# micro.net
KiCad netlist of a schematic drawn in Altium Designer
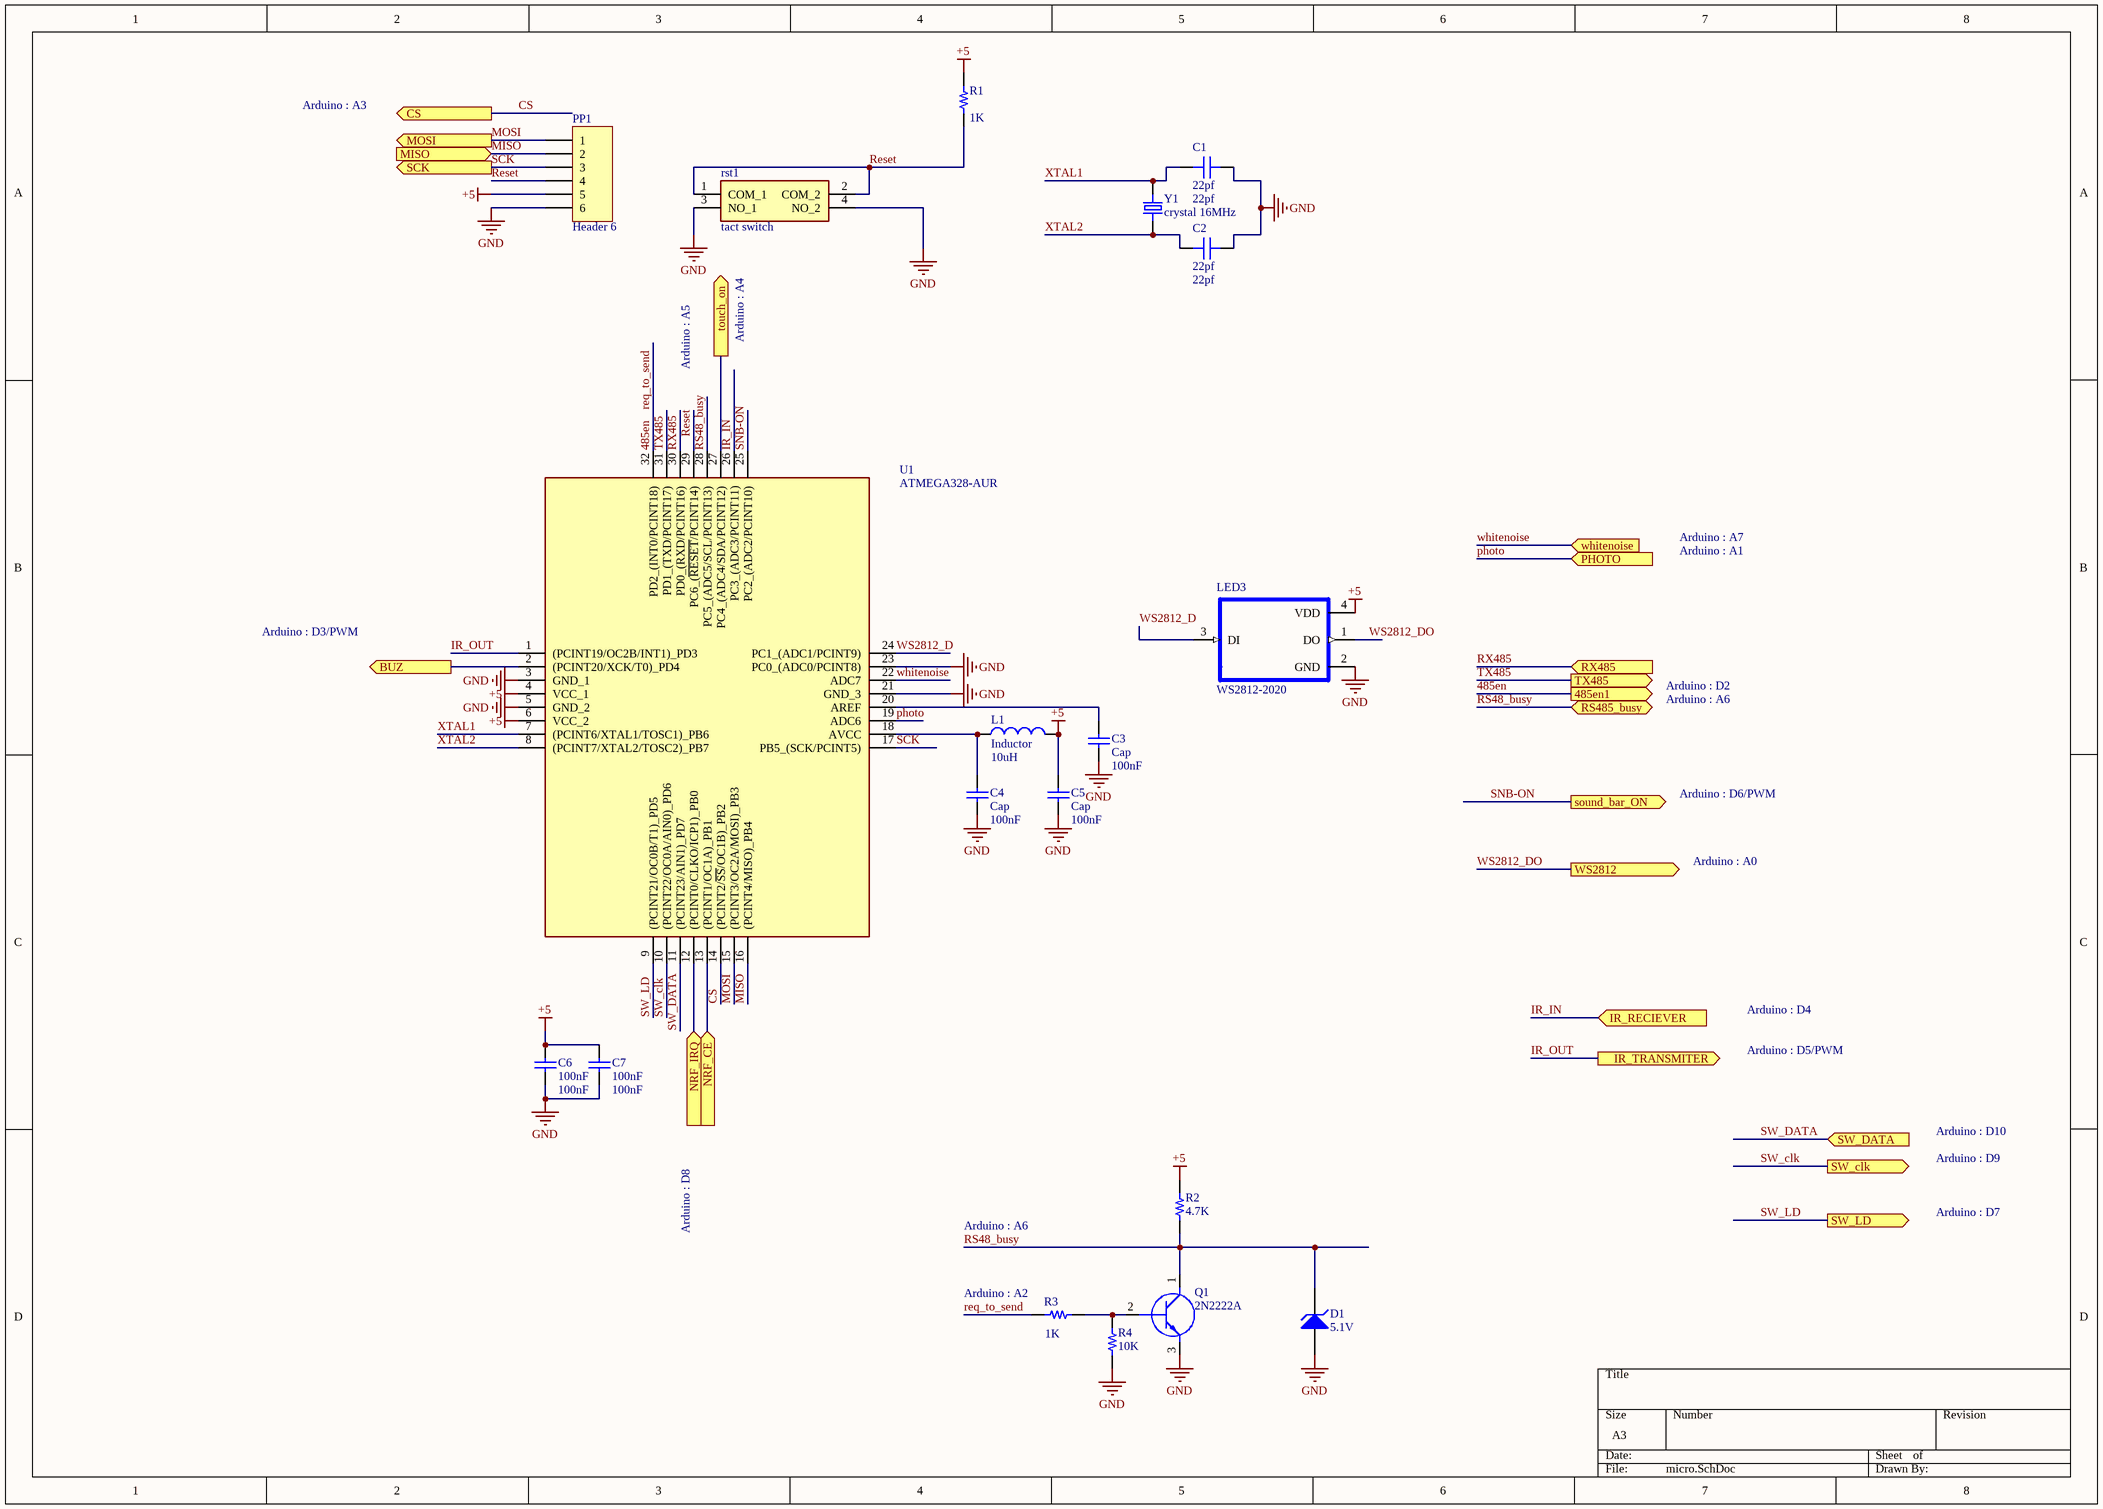
[diagram p0: micro.SchDoc]

(export (version "E")
  (design (tool "Eeschema 10.0.6"))
  (components
    (comp (ref "C1")
      (value "22pf")
      (footprint "0603C")
      (description "CAP SMD 0603")
      (fields (field (name "PART NUMBER") "C0805X106K9RAC7800") (field (name "ALTIUM_VALUE") "22pf"))
      (libsource (lib "lamp control-ver2") (part "Capacitor"))
    )
    (comp (ref "C2")
      (value "22pf")
      (footprint "0603C")
      (description "CAP SMD 0603")
      (fields (field (name "PART NUMBER") "C0805X106K9RAC7800") (field (name "ALTIUM_VALUE") "22pf"))
      (libsource (lib "lamp control-ver2") (part "Capacitor"))
    )
    (comp (ref "C3")
      (value "Cap")
      (footprint "0603C")
      (description "Capacitor")
      (fields (field (name "ALTIUM_VALUE") "100nF") (field (name "PUBLISHER") "Altium Limited"))
      (libsource (lib "Miscellaneous Devices") (part "Cap"))
    )
    (comp (ref "C4")
      (value "Cap")
      (footprint "0603C")
      (description "Capacitor")
      (fields (field (name "ALTIUM_VALUE") "100nF") (field (name "PUBLISHER") "Altium Limited"))
      (libsource (lib "Miscellaneous Devices") (part "Cap"))
    )
    (comp (ref "C5")
      (value "Cap")
      (footprint "0603C")
      (description "Capacitor")
      (fields (field (name "ALTIUM_VALUE") "100nF") (field (name "PUBLISHER") "Altium Limited"))
      (libsource (lib "Miscellaneous Devices") (part "Cap"))
    )
    (comp (ref "C6")
      (value "100nF")
      (footprint "0603C")
      (description "CAP SMD 0603")
      (fields (field (name "ALTIUM_VALUE") "100nF") (field (name "PUBLISHER") "Altium Limited"))
      (libsource (lib "Miscellaneous Devices") (part "Cap"))
    )
    (comp (ref "C7")
      (value "100nF")
      (footprint "0603C")
      (description "CAP SMD 0603")
      (fields (field (name "ALTIUM_VALUE") "100nF") (field (name "PUBLISHER") "Altium Limited"))
      (libsource (lib "Miscellaneous Devices") (part "Cap"))
    )
    (comp (ref "D1")
      (value "5.1V")
      (footprint "Diode 1n4148 SMD")
      (description "Zener Diode 5.1v")
      (fields (field (name "PUBLISHER") "Altium Limited"))
      (libsource (lib "Miscellaneous Devices") (part "D Zener"))
    )
    (comp (ref "L1")
      (value "Inductor")
      (footprint "IND1206")
      (fields (field (name "ALTIUM_VALUE") "10uH") (field (name "PUBLISHER") "Altium Limited"))
      (libsource (lib "Miscellaneous Devices") (part "Inductor"))
    )
    (comp (ref "LED3")
      (value "WS2812-2020")
      (footprint "LED_WS2812-2020")
      (description "Intelligent control LED integrated light source")
      (fields (field (name "MF") "Worldsemi"))
      (libsource (lib "WS2812") (part "WS2812-2020"))
    )
    (comp (ref "PP1")
      (value "Header 6")
      (footprint "HDR1X6")
      (description "Header, 6-Pin , female")
      (fields (field (name "PUBLISHER") "Altium Limited"))
      (libsource (lib "Miscellaneous Connectors") (part "Header 6"))
    )
    (comp (ref "Q1")
      (value "2N2222A")
      (footprint "soT95p280x130-3n")
      (description "Transistor BJT NPN SMD")
      (libsource (lib "*") (part "2N2222A"))
    )
    (comp (ref "R1")
      (value "1K")
      (footprint "0603R")
      (description "RES SMD 0603")
      (fields (field (name "PART NUMBER") "RCS0805100KFKEA"))
      (libsource (lib "lamp control-ver2") (part "Resistor"))
    )
    (comp (ref "R2")
      (value "4.7K")
      (footprint "0603R")
      (description "RES SMD 0603")
      (fields (field (name "PART NUMBER") "RCS0805100KFKEA"))
      (libsource (lib "lamp control-ver2") (part "Resistor"))
    )
    (comp (ref "R3")
      (value "1K")
      (footprint "0603R")
      (description "RES SMD 0603")
      (fields (field (name "PART NUMBER") "RCS0805100KFKEA"))
      (libsource (lib "lamp control-ver2") (part "Resistor"))
    )
    (comp (ref "R4")
      (value "10K")
      (footprint "0603R")
      (description "RES SMD 0603")
      (fields (field (name "PART NUMBER") "RCS0805100KFKEA"))
      (libsource (lib "lamp control-ver2") (part "Resistor"))
    )
    (comp (ref "rst1")
      (value "tact switch")
      (footprint "DTSM63NVB")
      (description "Push Button SMD - 4PIN")
      (fields
        (field (name "MANUFACTURER_PART_NUMBER") "DTSM-66R-V-T/R")
        (field (name "MOUSER PART NUMBER") "113-DTSM66RVTR")
      )
      (libsource (lib "*") (part "DTSM-66R-V-T_R"))
    )
    (comp (ref "U1")
      (value "ATMEGA328-AUR")
      (footprint "TQFP32_N")
      (description "Integrated Circuit")
      (fields (field (name "MOUSER PART NUMBER") "556-ATMEGA328-AUR"))
      (libsource (lib "*") (part "ATMEGA328-AUR"))
    )
    (comp (ref "Y1")
      (value "crystal 16MHz")
      (footprint "XTAL_ECS-180-S-5P-DN-TR")
      (description "Crystals 16MHz")
      (fields (field (name "MP") "ECS-180-S-5P-DN-TR") (field (name "MF") "ECS International"))
      (libsource (lib "CrystalSMD") (part "ECS-180-S-5P-DN-TR"))
    )
  )
  (nets
    (net (code "1") (name "+5") (class "Default")
      (node (ref "C5") (pin "1") (pinfunction "1_1") (pintype "passive"))
      (node (ref "C6") (pin "1") (pinfunction "1_1") (pintype "passive"))
      (node (ref "C7") (pin "1") (pinfunction "1_1") (pintype "passive"))
      (node (ref "L1") (pin "2") (pinfunction "2_2") (pintype "passive"))
      (node (ref "LED3") (pin "4") (pinfunction "VDD_4") (pintype "power_in"))
      (node (ref "PP1") (pin "5") (pinfunction "5_5") (pintype "passive"))
      (node (ref "R1") (pin "2") (pinfunction "2_2") (pintype "passive"))
      (node (ref "R2") (pin "1") (pinfunction "1_1") (pintype "passive"))
      (node (ref "U1") (pin "4") (pinfunction "VCC_1_4") (pintype "passive"))
      (node (ref "U1") (pin "6") (pinfunction "VCC_2_6") (pintype "passive"))
    )
    (net (code "2") (name "/485en") (class "Default")
      (node (ref "R3") (pin "2") (pinfunction "2_2") (pintype "passive"))
      (node (ref "U1") (pin "32") (pinfunction "PD2_(INT0/PCINT18)_32") (pintype "passive"))
    )
    (net (code "3") (name "/BUZ") (class "Default")
      (node (ref "U1") (pin "2") (pinfunction "(PCINT20/XCK/T0)_PD4_2") (pintype "passive"))
    )
    (net (code "4") (name "/CS") (class "Default")
      (node (ref "U1") (pin "14") (pinfunction "(PCINT2/~{SS}/OC1B)_PB2_14") (pintype "passive"))
    )
    (net (code "5") (name "/IR_IN") (class "Default")
      (node (ref "U1") (pin "26") (pinfunction "PC3_(ADC3/PCINT11)_26") (pintype "passive"))
    )
    (net (code "6") (name "/IR_OUT") (class "Default")
      (node (ref "U1") (pin "1") (pinfunction "(PCINT19/OC2B/INT1)_PD3_1") (pintype "passive"))
    )
    (net (code "7") (name "/MISO") (class "Default")
      (node (ref "PP1") (pin "2") (pinfunction "2_2") (pintype "passive"))
      (node (ref "U1") (pin "16") (pinfunction "(PCINT4/MISO)_PB4_16") (pintype "passive"))
    )
    (net (code "8") (name "/MOSI") (class "Default")
      (node (ref "PP1") (pin "1") (pinfunction "1_1") (pintype "passive"))
      (node (ref "U1") (pin "15") (pinfunction "(PCINT3/OC2A/MOSI)_PB3_15") (pintype "passive"))
    )
    (net (code "9") (name "/NRF_CE") (class "Default")
      (node (ref "U1") (pin "13") (pinfunction "(PCINT1/OC1A)_PB1_13") (pintype "passive"))
    )
    (net (code "10") (name "/NRF_IRQ") (class "Default")
      (node (ref "U1") (pin "12") (pinfunction "(PCINT0/CLKO/ICP1)_PB0_12") (pintype "passive"))
    )
    (net (code "11") (name "/RS48_busy") (class "Default")
      (node (ref "D1") (pin "2") (pinfunction "K_2") (pintype "passive"))
      (node (ref "Q1") (pin "1") (pinfunction "C_1") (pintype "passive"))
      (node (ref "R2") (pin "2") (pinfunction "2_2") (pintype "passive"))
      (node (ref "U1") (pin "28") (pinfunction "PC5_(ADC5/SCL/PCINT13)_28") (pintype "passive"))
    )
    (net (code "12") (name "/RX485") (class "Default")
      (node (ref "U1") (pin "30") (pinfunction "PD0_(RXD/PCINT16)_30") (pintype "passive"))
    )
    (net (code "13") (name "/Reset") (class "Default")
      (node (ref "PP1") (pin "4") (pinfunction "4_4") (pintype "passive"))
      (node (ref "R1") (pin "1") (pinfunction "1_1") (pintype "passive"))
      (node (ref "U1") (pin "29") (pinfunction "PC6_(~{RESET}/PCINT14)_29") (pintype "passive"))
      (node (ref "rst1") (pin "1") (pinfunction "COM_1_1") (pintype "passive"))
      (node (ref "rst1") (pin "2") (pinfunction "COM_2_2") (pintype "passive"))
    )
    (net (code "14") (name "/SCK") (class "Default")
      (node (ref "PP1") (pin "3") (pinfunction "3_3") (pintype "passive"))
      (node (ref "U1") (pin "17") (pinfunction "PB5_(SCK/PCINT5)_17") (pintype "passive"))
    )
    (net (code "15") (name "/SNB-ON") (class "Default")
      (node (ref "U1") (pin "25") (pinfunction "PC2_(ADC2/PCINT10)_25") (pintype "passive"))
    )
    (net (code "16") (name "/SW_DATA") (class "Default")
      (node (ref "U1") (pin "11") (pinfunction "(PCINT23/AIN1)_PD7_11") (pintype "passive"))
    )
    (net (code "17") (name "/SW_LD") (class "Default")
      (node (ref "U1") (pin "9") (pinfunction "(PCINT21/OC0B/T1)_PD5_9") (pintype "passive"))
    )
    (net (code "18") (name "/SW_clk") (class "Default")
      (node (ref "U1") (pin "10") (pinfunction "(PCINT22/OC0A/AIN0)_PD6_10") (pintype "passive"))
    )
    (net (code "19") (name "/TX485") (class "Default")
      (node (ref "U1") (pin "31") (pinfunction "PD1_(TXD/PCINT17)_31") (pintype "passive"))
    )
    (net (code "20") (name "/WS2812_D") (class "Default")
      (node (ref "LED3") (pin "3") (pinfunction "DI_3") (pintype "input"))
      (node (ref "U1") (pin "24") (pinfunction "PC1_(ADC1/PCINT9)_24") (pintype "passive"))
    )
    (net (code "21") (name "/WS2812_DO") (class "Default")
      (node (ref "LED3") (pin "1") (pinfunction "DO_1") (pintype "output"))
    )
    (net (code "22") (name "/XTAL1") (class "Default")
      (node (ref "C1") (pin "2") (pinfunction "2_2") (pintype "passive"))
      (node (ref "U1") (pin "7") (pinfunction "(PCINT6/XTAL1/TOSC1)_PB6_7") (pintype "passive"))
      (node (ref "Y1") (pin "2") (pinfunction "2_2") (pintype "passive"))
    )
    (net (code "23") (name "/XTAL2") (class "Default")
      (node (ref "C2") (pin "2") (pinfunction "2_2") (pintype "passive"))
      (node (ref "U1") (pin "8") (pinfunction "(PCINT7/XTAL2/TOSC2)_PB7_8") (pintype "passive"))
      (node (ref "Y1") (pin "1") (pinfunction "1_1") (pintype "passive"))
    )
    (net (code "24") (name "/photo") (class "Default")
      (node (ref "U1") (pin "19") (pinfunction "ADC6_19") (pintype "passive"))
    )
    (net (code "25") (name "/touch_on") (class "Default")
      (node (ref "U1") (pin "27") (pinfunction "PC4_(ADC4/SDA/PCINT12)_27") (pintype "passive"))
    )
    (net (code "26") (name "/whitenoise") (class "Default")
      (node (ref "U1") (pin "22") (pinfunction "ADC7_22") (pintype "passive"))
    )
    (net (code "27") (name "GND") (class "Default")
      (node (ref "C1") (pin "1") (pinfunction "1_1") (pintype "passive"))
      (node (ref "C2") (pin "1") (pinfunction "1_1") (pintype "passive"))
      (node (ref "C3") (pin "2") (pinfunction "2_2") (pintype "passive"))
      (node (ref "C4") (pin "2") (pinfunction "2_2") (pintype "passive"))
      (node (ref "C5") (pin "2") (pinfunction "2_2") (pintype "passive"))
      (node (ref "C6") (pin "2") (pinfunction "2_2") (pintype "passive"))
      (node (ref "C7") (pin "2") (pinfunction "2_2") (pintype "passive"))
      (node (ref "D1") (pin "1") (pinfunction "A_1") (pintype "passive"))
      (node (ref "LED3") (pin "2") (pinfunction "GND_2") (pintype "power_in"))
      (node (ref "PP1") (pin "6") (pinfunction "6_6") (pintype "passive"))
      (node (ref "Q1") (pin "3") (pinfunction "E_3") (pintype "passive"))
      (node (ref "R4") (pin "2") (pinfunction "2_2") (pintype "passive"))
      (node (ref "U1") (pin "21") (pinfunction "GND_3_21") (pintype "passive"))
      (node (ref "U1") (pin "23") (pinfunction "PC0_(ADC0/PCINT8)_23") (pintype "passive"))
      (node (ref "U1") (pin "3") (pinfunction "GND_1_3") (pintype "passive"))
      (node (ref "U1") (pin "5") (pinfunction "GND_2_5") (pintype "passive"))
      (node (ref "rst1") (pin "3") (pinfunction "NO_1_3") (pintype "passive"))
      (node (ref "rst1") (pin "4") (pinfunction "NO_2_4") (pintype "passive"))
    )
    (net (code "28") (name "Net-(Q1-B)") (class "Default")
      (node (ref "Q1") (pin "2") (pinfunction "B_2") (pintype "passive"))
      (node (ref "R3") (pin "1") (pinfunction "1_1") (pintype "passive"))
      (node (ref "R4") (pin "1") (pinfunction "1_1") (pintype "passive"))
    )
    (net (code "29") (name "Net-(U1-AREF)") (class "Default")
      (node (ref "C3") (pin "1") (pinfunction "1_1") (pintype "passive"))
      (node (ref "U1") (pin "20") (pinfunction "AREF_20") (pintype "passive"))
    )
    (net (code "30") (name "Net-(U1-AVCC)") (class "Default")
      (node (ref "C4") (pin "1") (pinfunction "1_1") (pintype "passive"))
      (node (ref "L1") (pin "1") (pinfunction "1_1") (pintype "passive"))
      (node (ref "U1") (pin "18") (pinfunction "AVCC_18") (pintype "passive"))
    )
  )
)
